# NTAG_I2C_plus_Class4_Antenna_v1.net
KiCad netlist of a schematic drawn in Altium Designer
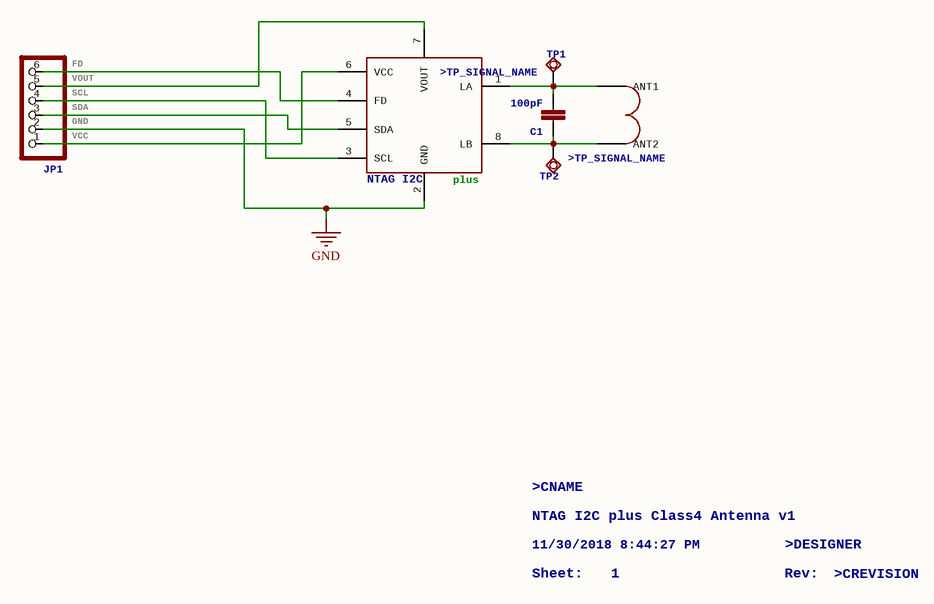
[diagram p0: NTAG I2C plus Class4 Antenna v1.SchDoc]

(export (version "E")
  (design (tool "Eeschema 10.0.6"))
  (components
    (comp (ref "C1")
      (value "100pF")
      (footprint "C0402K")
      (description "CAPACITOR, European symbol")
      (libsource (lib "rcl") (part "C-EUC0402K"))
    )
    (comp (ref "JP1")
      (value "PINHD-1X6/90")
      (footprint "1X06/90")
      (description "PIN HEADER")
      (fields (field (name "LIBRARYNAME") "pinhead (2)"))
      (libsource (lib "pinhead (2)") (part "PINHD-1X6/90"))
    )
    (comp (ref "TP1")
      (value "TPSQPAD1-13")
      (footprint "P1-13")
      (description "Test pad")
      (fields (field (name "TP_SIGNAL_NAME") ">TP_SIGNAL_NAME") (field (name "LIBRARYNAME") "testpad"))
      (libsource (lib "testpad") (part "TPSQPAD1-13"))
    )
    (comp (ref "TP2")
      (value "TPSQPAD1-13")
      (footprint "P1-13")
      (description "Test pad")
      (fields (field (name "TP_SIGNAL_NAME") ">TP_SIGNAL_NAME") (field (name "LIBRARYNAME") "testpad"))
      (libsource (lib "testpad") (part "TPSQPAD1-13"))
    )
    (comp (ref "U$1")
      (value "ENERGY-HARVESTING_3-TURNS54X27_3TURN_THIN")
      (footprint "54X27_3TURNS_THIN")
      (fields (field (name "LIBRARYNAME") "NTAG_Antennas"))
      (libsource (lib "NTAG_Antennas") (part "ENERGY-HARVESTING_3-TURNS54X27_3TURN_THIN"))
    )
    (comp (ref "U$3")
      (value "NTAG_I2CXQFN8")
      (footprint "SOT902-3")
      (fields (field (name "NTAGI2C") "NTAG I2C"))
      (libsource (lib "NTAG_I2C") (part "NTAG_I2CXQFN8"))
    )
  )
  (nets
    (net (code "1") (name "GND") (class "Default")
      (node (ref "JP1") (pin "2") (pinfunction "2_2") (pintype "passive"))
      (node (ref "U$3") (pin "2") (pinfunction "GND_2") (pintype "passive"))
    )
    (net (code "2") (name "Net-(U$3-FD)") (class "Default")
      (node (ref "JP1") (pin "6") (pinfunction "6_6") (pintype "passive"))
      (node (ref "U$3") (pin "4") (pinfunction "FD_4") (pintype "passive"))
    )
    (net (code "3") (name "Net-(U$3-LA)") (class "Default")
      (node (ref "C1") (pin "2") (pinfunction "2_2") (pintype "passive"))
      (node (ref "TP1") (pin "TP") (pinfunction "TP_TP") (pintype "passive"))
      (node (ref "U$1") (pin "ANT1") (pinfunction "ANT1_ANT1") (pintype "passive"))
      (node (ref "U$3") (pin "1") (pinfunction "LA_1") (pintype "passive"))
    )
    (net (code "4") (name "Net-(U$3-LB)") (class "Default")
      (node (ref "C1") (pin "1") (pinfunction "1_1") (pintype "passive"))
      (node (ref "TP2") (pin "TP") (pinfunction "TP_TP") (pintype "passive"))
      (node (ref "U$1") (pin "ANT2") (pinfunction "ANT2_ANT2") (pintype "passive"))
      (node (ref "U$3") (pin "8") (pinfunction "LB_8") (pintype "passive"))
    )
    (net (code "5") (name "Net-(U$3-SCL)") (class "Default")
      (node (ref "JP1") (pin "4") (pinfunction "4_4") (pintype "passive"))
      (node (ref "U$3") (pin "3") (pinfunction "SCL_3") (pintype "passive"))
    )
    (net (code "6") (name "Net-(U$3-SDA)") (class "Default")
      (node (ref "JP1") (pin "3") (pinfunction "3_3") (pintype "passive"))
      (node (ref "U$3") (pin "5") (pinfunction "SDA_5") (pintype "passive"))
    )
    (net (code "7") (name "Net-(U$3-VCC)") (class "Default")
      (node (ref "JP1") (pin "1") (pinfunction "1_1") (pintype "passive"))
      (node (ref "U$3") (pin "6") (pinfunction "VCC_6") (pintype "passive"))
    )
    (net (code "8") (name "Net-(U$3-VOUT)") (class "Default")
      (node (ref "JP1") (pin "5") (pinfunction "5_5") (pintype "passive"))
      (node (ref "U$3") (pin "7") (pinfunction "VOUT_7") (pintype "passive"))
    )
  )
)
